# SparkFun_Qwiic_Thermocouple_Amplifier_Sc.net
KiCad netlist of a schematic drawn in EAGLE
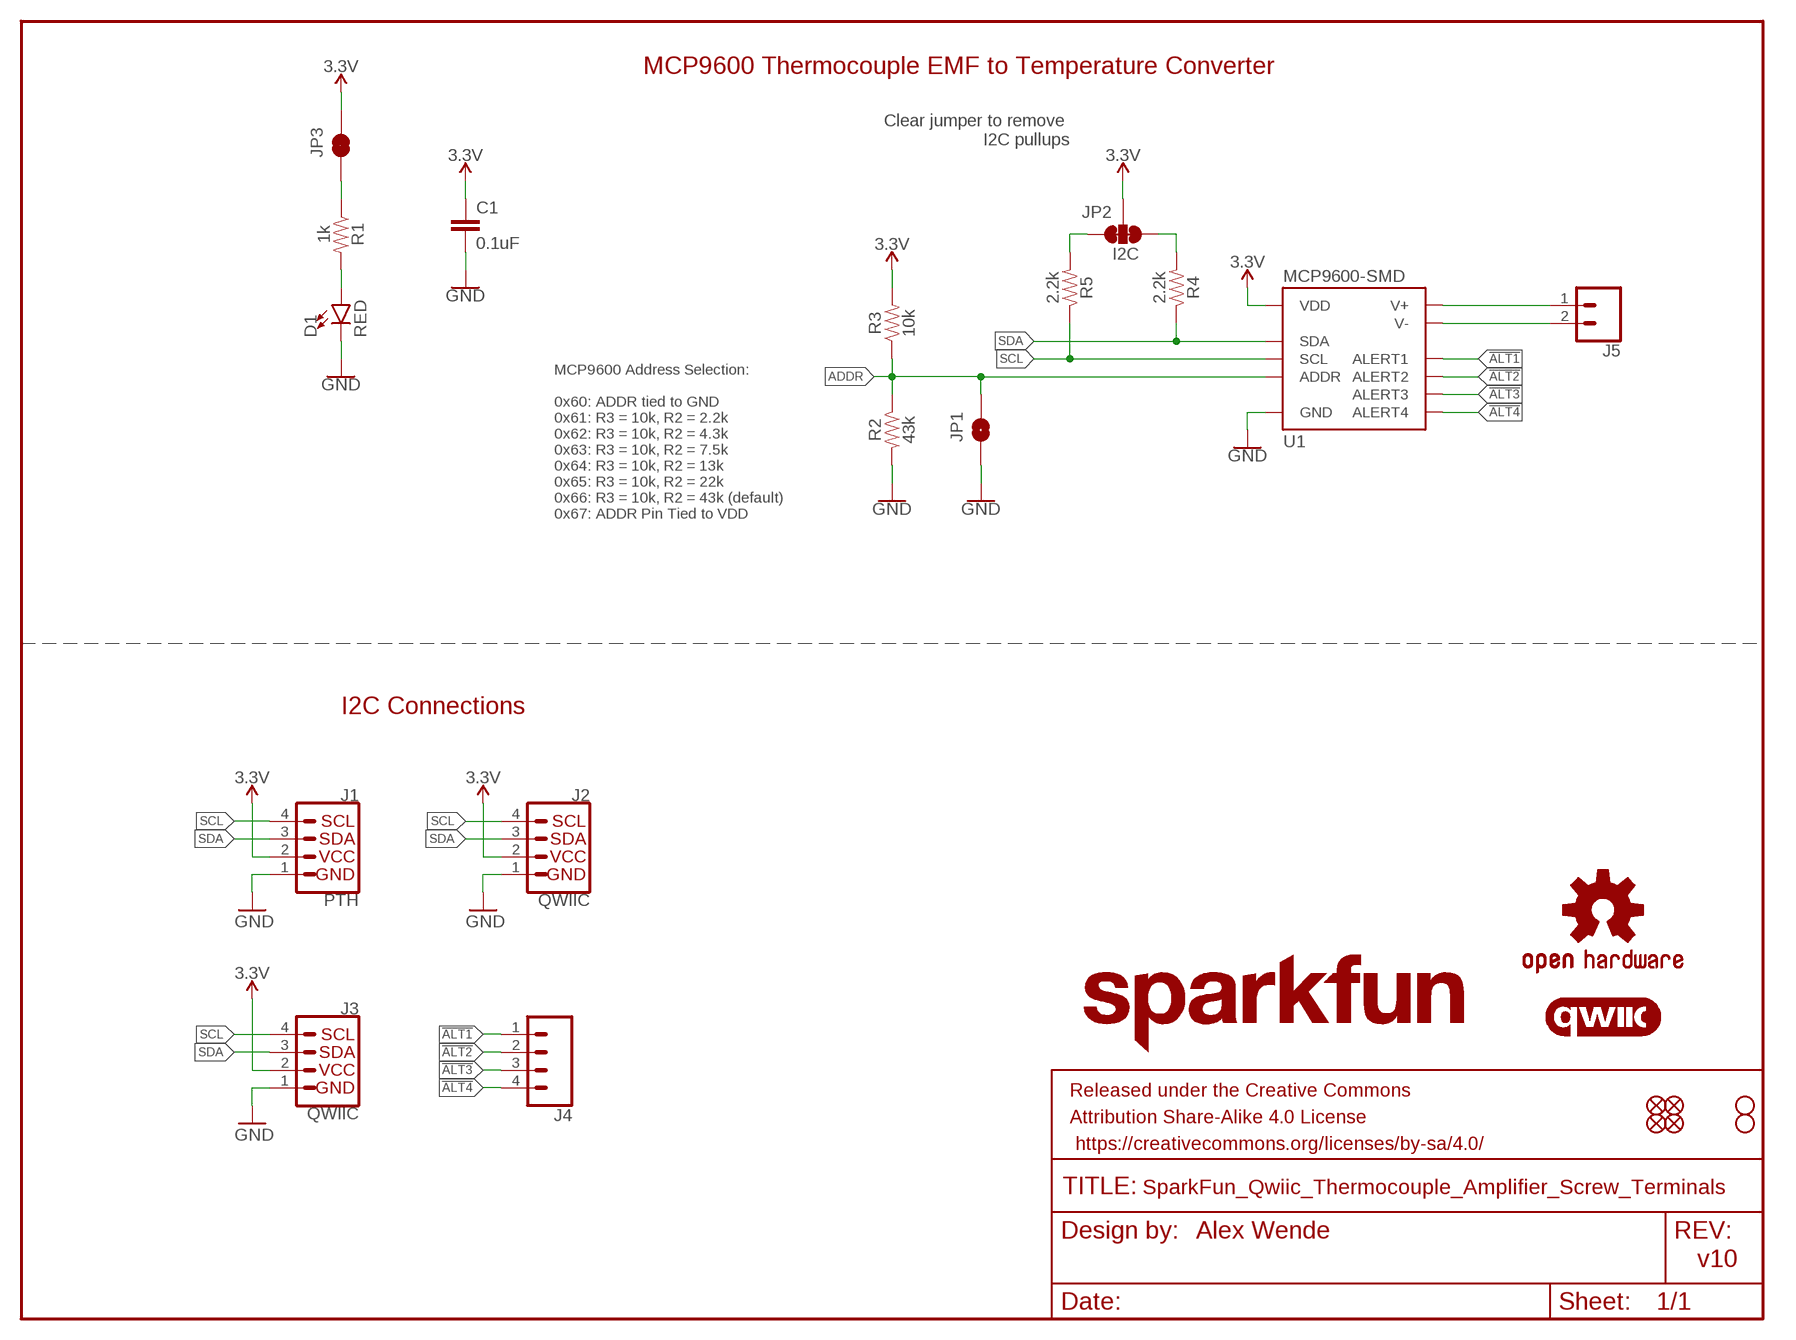
[diagram p0: schematic, sheet 1]

(export (version "E")
  (design (tool "Eeschema 10.0.6"))
  (components
    (comp (ref "C1")
      (value "0.1uF")
      (footprint "eagle-import:0603")
      (libsource (lib "eagle-import") (part "0.1UF-0603-25V-(+80/-20%)"))
    )
    (comp (ref "D1")
      (value "RED")
      (footprint "eagle-import:LED-0603")
      (libsource (lib "eagle-import") (part "LED-RED0603"))
    )
    (comp (ref "FD1")
      (value "FIDUCIALUFIDUCIAL")
      (footprint "eagle-import:FIDUCIAL-MICRO")
      (libsource (lib "eagle-import") (part "FIDUCIALUFIDUCIAL"))
    )
    (comp (ref "FD2")
      (value "FIDUCIALUFIDUCIAL")
      (footprint "eagle-import:FIDUCIAL-MICRO")
      (libsource (lib "eagle-import") (part "FIDUCIALUFIDUCIAL"))
    )
    (comp (ref "FD3")
      (value "FIDUCIALUFIDUCIAL")
      (footprint "eagle-import:FIDUCIAL-MICRO")
      (libsource (lib "eagle-import") (part "FIDUCIALUFIDUCIAL"))
    )
    (comp (ref "FD4")
      (value "FIDUCIALUFIDUCIAL")
      (footprint "eagle-import:FIDUCIAL-MICRO")
      (libsource (lib "eagle-import") (part "FIDUCIALUFIDUCIAL"))
    )
    (comp (ref "FRAME1")
      (value "FRAME-LETTER")
      (footprint "eagle-import:CREATIVE_COMMONS")
      (libsource (lib "eagle-import") (part "FRAME-LETTER"))
    )
    (comp (ref "J1")
      (value "PTH")
      (footprint "eagle-import:1X04_NO_SILK")
      (libsource (lib "eagle-import") (part "I2C_STANDARD_NO_SILK"))
    )
    (comp (ref "J2")
      (value "QWIIC")
      (footprint "eagle-import:JST04_1MM_RA")
      (libsource (lib "eagle-import") (part "QWIIC_CONNECTORJS-1MM"))
    )
    (comp (ref "J3")
      (value "QWIIC")
      (footprint "eagle-import:JST04_1MM_RA")
      (libsource (lib "eagle-import") (part "QWIIC_CONNECTORJS-1MM"))
    )
    (comp (ref "J4")
      (value "CONN_041X04_NO_SILK")
      (footprint "eagle-import:1X04_NO_SILK")
      (libsource (lib "eagle-import") (part "CONN_041X04_NO_SILK"))
    )
    (comp (ref "J5")
      (value "CONN_023.5MM")
      (footprint "eagle-import:SCREWTERMINAL-3.5MM-2")
      (libsource (lib "eagle-import") (part "CONN_023.5MM"))
    )
    (comp (ref "JP1")
      (value "JUMPER-SMT_2_NO_SILK")
      (footprint "eagle-import:SMT-JUMPER_2_NO_SILK")
      (libsource (lib "eagle-import") (part "JUMPER-SMT_2_NO_SILK"))
    )
    (comp (ref "JP2")
      (value "I2C")
      (footprint "eagle-import:SMT-JUMPER_3_2-NC_TRACE_SILK")
      (libsource (lib "eagle-import") (part "JUMPER-SMT_3_2-NC_TRACE_SILK"))
    )
    (comp (ref "JP3")
      (value "JUMPER-SMT_2_NC_TRACE_SILK")
      (footprint "eagle-import:SMT-JUMPER_2_NC_TRACE_SILK")
      (libsource (lib "eagle-import") (part "JUMPER-SMT_2_NC_TRACE_SILK"))
    )
    (comp (ref "JP8")
      (value "STAND-OFF")
      (footprint "eagle-import:STAND-OFF")
      (libsource (lib "eagle-import") (part "STAND-OFF"))
    )
    (comp (ref "JP9")
      (value "STAND-OFF")
      (footprint "eagle-import:STAND-OFF")
      (libsource (lib "eagle-import") (part "STAND-OFF"))
    )
    (comp (ref "LOGO1")
      (value "OSHW-LOGOMINI")
      (footprint "eagle-import:OSHW-LOGO-MINI")
      (libsource (lib "eagle-import") (part "OSHW-LOGOMINI"))
    )
    (comp (ref "LOGO2")
      (value "SFE_LOGO_NAME.1_INCH")
      (footprint "eagle-import:SFE_LOGO_NAME_.1")
      (libsource (lib "eagle-import") (part "SFE_LOGO_NAME.1_INCH"))
    )
    (comp (ref "LOGO3")
      (value "QWIIC_LOGO_5MM")
      (footprint "eagle-import:QWIIC_5MM")
      (libsource (lib "eagle-import") (part "QWIIC_LOGO_5MM"))
    )
    (comp (ref "R1")
      (value "1k")
      (footprint "eagle-import:0603")
      (libsource (lib "eagle-import") (part "1KOHM-0603-1/10W-1%"))
    )
    (comp (ref "R2")
      (value "43k")
      (footprint "eagle-import:0603")
      (libsource (lib "eagle-import") (part "43KOHM-0603-1/10W-1%"))
    )
    (comp (ref "R3")
      (value "10k")
      (footprint "eagle-import:0603")
      (libsource (lib "eagle-import") (part "10KOHM-0603-1/10W-1%"))
    )
    (comp (ref "R4")
      (value "2.2k")
      (footprint "eagle-import:0603")
      (libsource (lib "eagle-import") (part "2.2KOHM-0603-1/10W-1%"))
    )
    (comp (ref "R5")
      (value "2.2k")
      (footprint "eagle-import:0603")
      (libsource (lib "eagle-import") (part "2.2KOHM-0603-1/10W-1%"))
    )
    (comp (ref "U1")
      (value "MCP9600-SMD")
      (footprint "eagle-import:MQFN-20")
      (libsource (lib "eagle-import") (part "MCP9600-SMD"))
    )
  )
  (nets
    (net (code "1") (name "/~{ALT1}") (class "Default")
      (node (ref "J4") (pin "1") (pinfunction "1_1") (pintype "passive"))
      (node (ref "U1") (pin "11") (pinfunction "ALERT1_11") (pintype "bidirectional"))
    )
    (net (code "2") (name "/~{ALT2}") (class "Default")
      (node (ref "J4") (pin "2") (pinfunction "2_2") (pintype "passive"))
      (node (ref "U1") (pin "12") (pinfunction "ALERT2_12") (pintype "bidirectional"))
    )
    (net (code "3") (name "/~{ALT3}") (class "Default")
      (node (ref "J4") (pin "3") (pinfunction "3_3") (pintype "passive"))
      (node (ref "U1") (pin "14") (pinfunction "ALERT3_14") (pintype "bidirectional"))
    )
    (net (code "4") (name "/~{ALT4}") (class "Default")
      (node (ref "J4") (pin "4") (pinfunction "4_4") (pintype "passive"))
      (node (ref "U1") (pin "15") (pinfunction "ALERT4_15") (pintype "bidirectional"))
    )
    (net (code "5") (name "3.3V") (class "Default")
      (node (ref "C1") (pin "1") (pinfunction "1_1") (pintype "passive"))
      (node (ref "J1") (pin "2") (pinfunction "2_2") (pintype "power_in"))
      (node (ref "J2") (pin "2") (pinfunction "2_2") (pintype "power_in"))
      (node (ref "J3") (pin "2") (pinfunction "2_2") (pintype "power_in"))
      (node (ref "JP2") (pin "2") (pinfunction "2_2") (pintype "passive"))
      (node (ref "JP3") (pin "1") (pinfunction "1_1") (pintype "passive"))
      (node (ref "R3") (pin "2") (pinfunction "2_2") (pintype "passive"))
      (node (ref "U1") (pin "8") (pinfunction "VDD_8") (pintype "bidirectional"))
    )
    (net (code "6") (name "ADDR") (class "Default")
      (node (ref "JP1") (pin "1") (pinfunction "1_1") (pintype "passive"))
      (node (ref "R2") (pin "1") (pinfunction "1_1") (pintype "passive"))
      (node (ref "R3") (pin "1") (pinfunction "1_1") (pintype "passive"))
      (node (ref "U1") (pin "16") (pinfunction "ADDR_16") (pintype "bidirectional"))
    )
    (net (code "7") (name "GND") (class "Default")
      (node (ref "C1") (pin "2") (pinfunction "2_2") (pintype "passive"))
      (node (ref "D1") (pin "C") (pinfunction "C_C") (pintype "passive"))
      (node (ref "J1") (pin "1") (pinfunction "1_1") (pintype "power_in"))
      (node (ref "J2") (pin "1") (pinfunction "1_1") (pintype "power_in"))
      (node (ref "J3") (pin "1") (pinfunction "1_1") (pintype "power_in"))
      (node (ref "JP1") (pin "2") (pinfunction "2_2") (pintype "passive"))
      (node (ref "R2") (pin "2") (pinfunction "2_2") (pintype "passive"))
      (node (ref "U1") (pin "1") (pinfunction "GND_1") (pintype "bidirectional"))
      (node (ref "U1") (pin "10") (pinfunction "GND_10") (pintype "bidirectional"))
      (node (ref "U1") (pin "13") (pinfunction "GND_13") (pintype "bidirectional"))
      (node (ref "U1") (pin "17") (pinfunction "GND_17") (pintype "bidirectional"))
      (node (ref "U1") (pin "18") (pinfunction "GND_18") (pintype "bidirectional"))
      (node (ref "U1") (pin "21") (pinfunction "GND_21") (pintype "bidirectional"))
      (node (ref "U1") (pin "3") (pinfunction "GND_3") (pintype "bidirectional"))
      (node (ref "U1") (pin "5") (pinfunction "GND_5") (pintype "bidirectional"))
      (node (ref "U1") (pin "6") (pinfunction "GND_6") (pintype "bidirectional"))
      (node (ref "U1") (pin "7") (pinfunction "GND_7") (pintype "bidirectional"))
      (node (ref "U1") (pin "9") (pinfunction "GND_9") (pintype "bidirectional"))
    )
    (net (code "8") (name "Net-(D1-PadA)") (class "Default")
      (node (ref "D1") (pin "A") (pinfunction "A_A") (pintype "passive"))
      (node (ref "R1") (pin "2") (pinfunction "2_2") (pintype "passive"))
    )
    (net (code "9") (name "Net-(JP2-Pad1)") (class "Default")
      (node (ref "JP2") (pin "1") (pinfunction "1_1") (pintype "passive"))
      (node (ref "R5") (pin "2") (pinfunction "2_2") (pintype "passive"))
    )
    (net (code "10") (name "Net-(JP2-Pad3)") (class "Default")
      (node (ref "JP2") (pin "3") (pinfunction "3_3") (pintype "passive"))
      (node (ref "R4") (pin "2") (pinfunction "2_2") (pintype "passive"))
    )
    (net (code "11") (name "Net-(JP3-Pad2)") (class "Default")
      (node (ref "JP3") (pin "2") (pinfunction "2_2") (pintype "passive"))
      (node (ref "R1") (pin "1") (pinfunction "1_1") (pintype "passive"))
    )
    (net (code "12") (name "Net-(U1-V+)") (class "Default")
      (node (ref "J5") (pin "1") (pinfunction "1_1") (pintype "passive"))
      (node (ref "U1") (pin "2") (pinfunction "V+_2") (pintype "bidirectional"))
    )
    (net (code "13") (name "Net-(U1-V-)") (class "Default")
      (node (ref "J5") (pin "2") (pinfunction "2_2") (pintype "passive"))
      (node (ref "U1") (pin "4") (pinfunction "V-_4") (pintype "bidirectional"))
    )
    (net (code "14") (name "SCL") (class "Default")
      (node (ref "J1") (pin "4") (pinfunction "4_4") (pintype "passive"))
      (node (ref "J2") (pin "4") (pinfunction "4_4") (pintype "passive"))
      (node (ref "J3") (pin "4") (pinfunction "4_4") (pintype "passive"))
      (node (ref "R5") (pin "1") (pinfunction "1_1") (pintype "passive"))
      (node (ref "U1") (pin "19") (pinfunction "SCL_19") (pintype "bidirectional"))
    )
    (net (code "15") (name "SDA") (class "Default")
      (node (ref "J1") (pin "3") (pinfunction "3_3") (pintype "passive"))
      (node (ref "J2") (pin "3") (pinfunction "3_3") (pintype "passive"))
      (node (ref "J3") (pin "3") (pinfunction "3_3") (pintype "passive"))
      (node (ref "R4") (pin "1") (pinfunction "1_1") (pintype "passive"))
      (node (ref "U1") (pin "20") (pinfunction "SDA_20") (pintype "bidirectional"))
    )
  )
)
